# tweeq-Stamp_Prox_VCNL4020.net
KiCad netlist of a schematic drawn in EAGLE
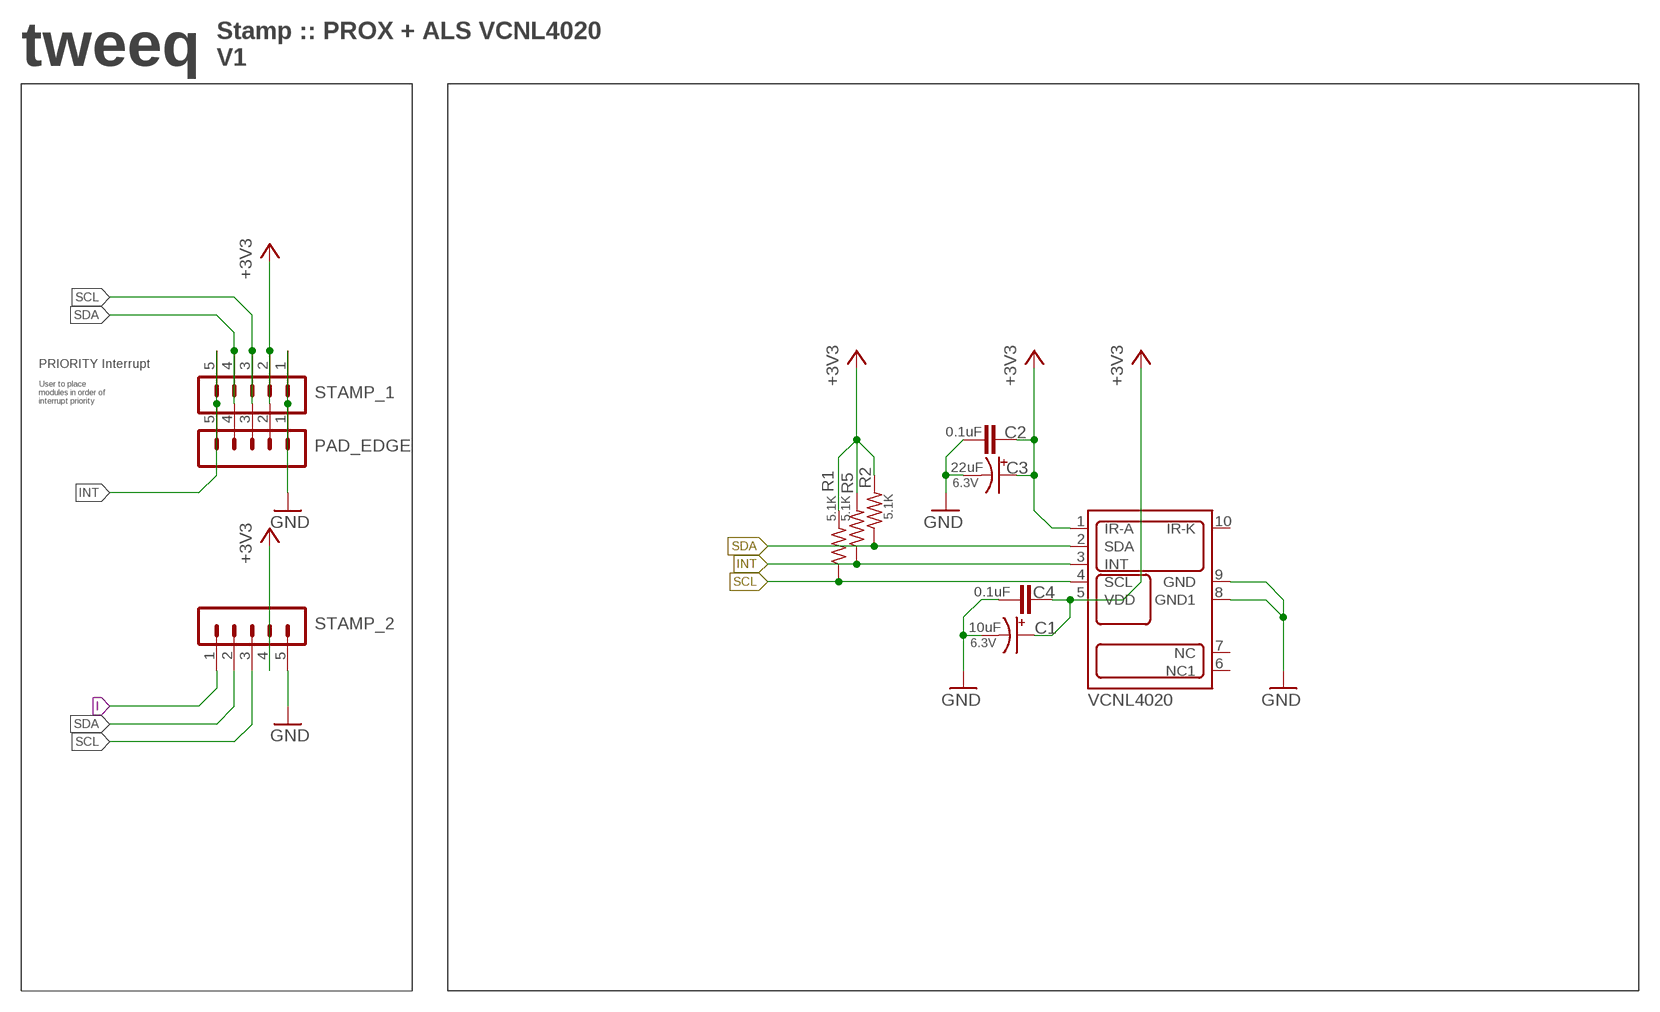
[diagram p0: schematic, sheet 1]

(export (version "E")
  (design (tool "Eeschema 10.0.6"))
  (components
    (comp (ref "C1")
      (value "10uF")
      (footprint "eagle-import:SMC_Z")
      (libsource (lib "eagle-import") (part "CPOL-USSMCZ"))
    )
    (comp (ref "C2")
      (value "0.1uF")
      (footprint "eagle-import:C0402K")
      (libsource (lib "eagle-import") (part "C-EUC0402K"))
    )
    (comp (ref "C3")
      (value "22uF")
      (footprint "eagle-import:SMC_Z")
      (libsource (lib "eagle-import") (part "CPOL-USSMCZ"))
    )
    (comp (ref "C4")
      (value "0.1uF")
      (footprint "eagle-import:C0402K")
      (libsource (lib "eagle-import") (part "C-EUC0402K"))
    )
    (comp (ref "PAD_EDGE")
      (value "M05-11.5MM-PAD")
      (footprint "eagle-import:1X05-1.5MM-PAD")
      (libsource (lib "eagle-import") (part "M05-11.5MM-PAD"))
    )
    (comp (ref "R1")
      (value "5.1K")
      (footprint "eagle-import:R0402")
      (libsource (lib "eagle-import") (part "R-US_R0402"))
    )
    (comp (ref "R2")
      (value "5.1K")
      (footprint "eagle-import:R0402")
      (libsource (lib "eagle-import") (part "R-US_R0402"))
    )
    (comp (ref "R5")
      (value "5.1K")
      (footprint "eagle-import:R0402")
      (libsource (lib "eagle-import") (part "R-US_R0402"))
    )
    (comp (ref "STAMP_1")
      (value "M05-1STAMP")
      (footprint "eagle-import:1X05-1.5MM-STAMP")
      (libsource (lib "eagle-import") (part "M05-1STAMP"))
    )
    (comp (ref "STAMP_2")
      (value "M05-1STAMP")
      (footprint "eagle-import:1X05-1.5MM-STAMP")
      (libsource (lib "eagle-import") (part "M05-1STAMP"))
    )
    (comp (ref "VCNL4020")
      (value "VCNL4020")
      (footprint "eagle-import:VCNL4020")
      (libsource (lib "eagle-import") (part "VCNL4020"))
    )
  )
  (nets
    (net (code "1") (name "+3V3") (class "Default")
      (node (ref "C1") (pin "+") (pinfunction "+_+") (pintype "passive"))
      (node (ref "C2") (pin "2") (pinfunction "2_2") (pintype "passive"))
      (node (ref "C3") (pin "+") (pinfunction "+_+") (pintype "passive"))
      (node (ref "C4") (pin "2") (pinfunction "2_2") (pintype "passive"))
      (node (ref "PAD_EDGE") (pin "2") (pinfunction "2_2") (pintype "passive"))
      (node (ref "R1") (pin "2") (pinfunction "2_2") (pintype "passive"))
      (node (ref "R2") (pin "2") (pinfunction "2_2") (pintype "passive"))
      (node (ref "R5") (pin "2") (pinfunction "2_2") (pintype "passive"))
      (node (ref "STAMP_1") (pin "2") (pinfunction "2_2") (pintype "passive"))
      (node (ref "STAMP_2") (pin "4") (pinfunction "4_4") (pintype "passive"))
      (node (ref "VCNL4020") (pin "1") (pinfunction "IR-A_1") (pintype "bidirectional"))
      (node (ref "VCNL4020") (pin "5") (pinfunction "VDD_5") (pintype "bidirectional"))
    )
    (net (code "2") (name "GND") (class "Default")
      (node (ref "C1") (pin "-") (pinfunction "-_-") (pintype "passive"))
      (node (ref "C2") (pin "1") (pinfunction "1_1") (pintype "passive"))
      (node (ref "C3") (pin "-") (pinfunction "-_-") (pintype "passive"))
      (node (ref "C4") (pin "1") (pinfunction "1_1") (pintype "passive"))
      (node (ref "PAD_EDGE") (pin "1") (pinfunction "1_1") (pintype "passive"))
      (node (ref "STAMP_1") (pin "1") (pinfunction "1_1") (pintype "passive"))
      (node (ref "STAMP_2") (pin "5") (pinfunction "5_5") (pintype "passive"))
      (node (ref "VCNL4020") (pin "8") (pinfunction "GND1_8") (pintype "bidirectional"))
      (node (ref "VCNL4020") (pin "9") (pinfunction "GND_9") (pintype "bidirectional"))
    )
    (net (code "3") (name "I") (class "Default")
      (node (ref "STAMP_2") (pin "1") (pinfunction "1_1") (pintype "passive"))
    )
    (net (code "4") (name "INT") (class "Default")
      (node (ref "PAD_EDGE") (pin "5") (pinfunction "5_5") (pintype "passive"))
      (node (ref "R5") (pin "1") (pinfunction "1_1") (pintype "passive"))
      (node (ref "STAMP_1") (pin "5") (pinfunction "5_5") (pintype "passive"))
      (node (ref "VCNL4020") (pin "3") (pinfunction "INT_3") (pintype "bidirectional"))
    )
    (net (code "5") (name "SCL") (class "Default")
      (node (ref "PAD_EDGE") (pin "3") (pinfunction "3_3") (pintype "passive"))
      (node (ref "R1") (pin "1") (pinfunction "1_1") (pintype "passive"))
      (node (ref "STAMP_1") (pin "3") (pinfunction "3_3") (pintype "passive"))
      (node (ref "STAMP_2") (pin "3") (pinfunction "3_3") (pintype "passive"))
      (node (ref "VCNL4020") (pin "4") (pinfunction "SCL_4") (pintype "bidirectional"))
    )
    (net (code "6") (name "SDA") (class "Default")
      (node (ref "PAD_EDGE") (pin "4") (pinfunction "4_4") (pintype "passive"))
      (node (ref "R2") (pin "1") (pinfunction "1_1") (pintype "passive"))
      (node (ref "STAMP_1") (pin "4") (pinfunction "4_4") (pintype "passive"))
      (node (ref "STAMP_2") (pin "2") (pinfunction "2_2") (pintype "passive"))
      (node (ref "VCNL4020") (pin "2") (pinfunction "SDA_2") (pintype "bidirectional"))
    )
    (net (code "7") (name "unconnected-(VCNL4020-IR-K-Pad10)") (class "Default")
      (node (ref "VCNL4020") (pin "10") (pinfunction "IR-K_10") (pintype "bidirectional"))
    )
    (net (code "8") (name "unconnected-(VCNL4020-NC-Pad7)") (class "Default")
      (node (ref "VCNL4020") (pin "7") (pinfunction "NC_7") (pintype "no_connect"))
    )
    (net (code "9") (name "unconnected-(VCNL4020-NC1-Pad6)") (class "Default")
      (node (ref "VCNL4020") (pin "6") (pinfunction "NC1_6") (pintype "no_connect"))
    )
  )
)
